# board.net
KiCad netlist of a schematic drawn in EAGLE
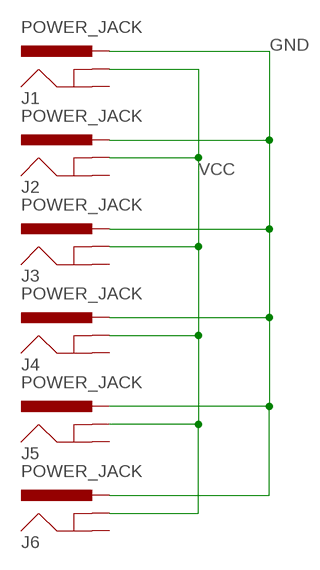
[diagram p0: schematic, sheet 1]

(export (version "E")
  (design (tool "Eeschema 10.0.6"))
  (components
    (comp (ref "J1")
      (value "POWER_JACK")
      (footprint "eagle-import:POWER_JACK_PTH")
      (libsource (lib "eagle-import") (part "POWER_JACK"))
    )
    (comp (ref "J2")
      (value "POWER_JACK")
      (footprint "eagle-import:POWER_JACK_PTH")
      (libsource (lib "eagle-import") (part "POWER_JACK"))
    )
    (comp (ref "J3")
      (value "POWER_JACK")
      (footprint "eagle-import:POWER_JACK_PTH")
      (libsource (lib "eagle-import") (part "POWER_JACK"))
    )
    (comp (ref "J4")
      (value "POWER_JACK")
      (footprint "eagle-import:POWER_JACK_PTH")
      (libsource (lib "eagle-import") (part "POWER_JACK"))
    )
    (comp (ref "J5")
      (value "POWER_JACK")
      (footprint "eagle-import:POWER_JACK_PTH")
      (libsource (lib "eagle-import") (part "POWER_JACK"))
    )
    (comp (ref "J6")
      (value "POWER_JACK")
      (footprint "eagle-import:POWER_JACK_PTH")
      (libsource (lib "eagle-import") (part "POWER_JACK"))
    )
  )
  (nets
    (net (code "1") (name "/GND") (class "Default")
      (node (ref "J1") (pin "PWR") (pinfunction "PWR_PWR") (pintype "bidirectional"))
      (node (ref "J2") (pin "PWR") (pinfunction "PWR_PWR") (pintype "bidirectional"))
      (node (ref "J3") (pin "PWR") (pinfunction "PWR_PWR") (pintype "bidirectional"))
      (node (ref "J4") (pin "PWR") (pinfunction "PWR_PWR") (pintype "bidirectional"))
      (node (ref "J5") (pin "PWR") (pinfunction "PWR_PWR") (pintype "bidirectional"))
      (node (ref "J6") (pin "PWR") (pinfunction "PWR_PWR") (pintype "bidirectional"))
    )
    (net (code "2") (name "/VCC") (class "Default")
      (node (ref "J1") (pin "GNDBREAK") (pinfunction "GNDBREAK_GNDBREAK") (pintype "bidirectional"))
      (node (ref "J2") (pin "GNDBREAK") (pinfunction "GNDBREAK_GNDBREAK") (pintype "bidirectional"))
      (node (ref "J3") (pin "GNDBREAK") (pinfunction "GNDBREAK_GNDBREAK") (pintype "bidirectional"))
      (node (ref "J4") (pin "GNDBREAK") (pinfunction "GNDBREAK_GNDBREAK") (pintype "bidirectional"))
      (node (ref "J5") (pin "GNDBREAK") (pinfunction "GNDBREAK_GNDBREAK") (pintype "bidirectional"))
      (node (ref "J6") (pin "GNDBREAK") (pinfunction "GNDBREAK_GNDBREAK") (pintype "bidirectional"))
    )
    (net (code "3") (name "unconnected-(J1-PadGND)") (class "Default")
      (node (ref "J1") (pin "GND") (pinfunction "GND_GND") (pintype "bidirectional"))
    )
    (net (code "4") (name "unconnected-(J2-PadGND)") (class "Default")
      (node (ref "J2") (pin "GND") (pinfunction "GND_GND") (pintype "bidirectional"))
    )
    (net (code "5") (name "unconnected-(J3-PadGND)") (class "Default")
      (node (ref "J3") (pin "GND") (pinfunction "GND_GND") (pintype "bidirectional"))
    )
    (net (code "6") (name "unconnected-(J4-PadGND)") (class "Default")
      (node (ref "J4") (pin "GND") (pinfunction "GND_GND") (pintype "bidirectional"))
    )
    (net (code "7") (name "unconnected-(J5-PadGND)") (class "Default")
      (node (ref "J5") (pin "GND") (pinfunction "GND_GND") (pintype "bidirectional"))
    )
    (net (code "8") (name "unconnected-(J6-PadGND)") (class "Default")
      (node (ref "J6") (pin "GND") (pinfunction "GND_GND") (pintype "bidirectional"))
    )
  )
)
